# 3V3.net
KiCad netlist of a schematic drawn in Altium Designer
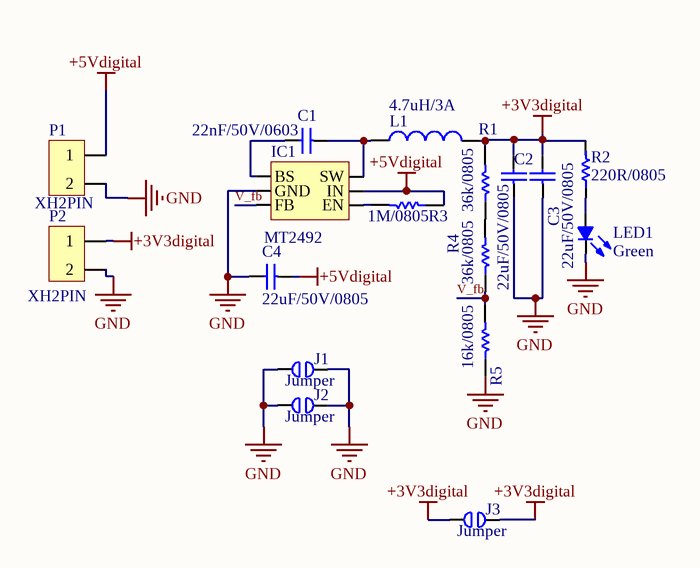
[diagram p0: 3V3.SchDoc]

(export (version "E")
  (design (tool "Eeschema 10.0.6"))
  (components
    (comp (ref "C1")
      (value "22nF/50V/0603")
      (footprint "cap 0603")
      (description "Capacitor")
      (libsource (lib "Schlib") (part "Capacitor"))
    )
    (comp (ref "C2")
      (value "22uF/50V/0805")
      (footprint "CAP 0805")
      (description "Capacitor")
      (libsource (lib "Schlib") (part "Capacitor"))
    )
    (comp (ref "C3")
      (value "22uF/50V/0805")
      (footprint "CAP 0805")
      (description "Capacitor")
      (libsource (lib "Schlib") (part "Capacitor"))
    )
    (comp (ref "C4")
      (value "22uF/50V/0805")
      (footprint "CAP 0805")
      (description "Capacitor")
      (libsource (lib "Schlib") (part "Capacitor"))
    )
    (comp (ref "IC1") (value "MT2492") (footprint "SOT23-6") (libsource (lib "Schlib") (part "ME3116AM6G")))
    (comp (ref "J1") (value "Jumper") (footprint "JUMPER 11MM") (libsource (lib "Schlib") (part "Jumper")))
    (comp (ref "J2") (value "Jumper") (footprint "JUMPER 11MM") (libsource (lib "Schlib") (part "Jumper")))
    (comp (ref "J3") (value "Jumper") (footprint "JUMPER 11MM") (libsource (lib "Schlib") (part "Jumper")))
    (comp (ref "L1")
      (value "4.7uH/3A")
      (footprint "5030")
      (description "Inductor")
      (libsource (lib "PFC NCP1653A 1KW") (part "Inductor"))
    )
    (comp (ref "LED1")
      (value "LED 3mm/Green")
      (footprint "LED 3mm")
      (description "Typical LED")
      (fields (field (name "COLOR") "Green"))
      (libsource (lib "TL494 12V-20A-KARA") (part "LED"))
    )
    (comp (ref "P1")
      (value "XH2PIN")
      (footprint "pin-header 2*1")
      (description "RELAY")
      (fields (field (name "PUBLISHER") "Altium Limited"))
      (libsource (lib "Schlib") (part "Header 2H"))
    )
    (comp (ref "P2")
      (value "XH2PIN")
      (footprint "pin-header 2*1")
      (description "RELAY")
      (fields (field (name "PUBLISHER") "Altium Limited"))
      (libsource (lib "Schlib") (part "Header 2H"))
    )
    (comp (ref "R1")
      (value "36k/0805")
      (footprint "Resistor 0603")
      (description "Resistor")
      (fields (field (name "PUBLISHER") "Altium Limited"))
      (libsource (lib "Miscellaneous Devices") (part "Res1"))
    )
    (comp (ref "R2") (value "220R/0805") (footprint "RES 0805") (libsource (lib "Schlib") (part "Res")))
    (comp (ref "R3")
      (value "1M/0805")
      (footprint "RES 0805")
      (description "Resistor")
      (fields (field (name "PUBLISHER") "Altium Limited"))
      (libsource (lib "Miscellaneous Devices") (part "Res1"))
    )
    (comp (ref "R4")
      (value "36k/0805")
      (footprint "Resistor 0603")
      (description "Resistor")
      (fields (field (name "PUBLISHER") "Altium Limited"))
      (libsource (lib "Miscellaneous Devices") (part "Res1"))
    )
    (comp (ref "R5")
      (value "16k/0805")
      (footprint "Resistor 0603")
      (description "Resistor")
      (fields (field (name "PUBLISHER") "Altium Limited"))
      (libsource (lib "Miscellaneous Devices") (part "Res1"))
    )
  )
  (nets
    (net (code "1") (name "+3V3digital") (class "Default")
      (node (ref "C2") (pin "1") (pinfunction "+_1") (pintype "passive"))
      (node (ref "C3") (pin "1") (pinfunction "+_1") (pintype "passive"))
      (node (ref "J3") (pin "1") (pinfunction "1_1") (pintype "passive"))
      (node (ref "J3") (pin "2") (pinfunction "2_2") (pintype "passive"))
      (node (ref "L1") (pin "2") (pinfunction "2_2") (pintype "passive"))
      (node (ref "P2") (pin "1") (pinfunction "1_1") (pintype "passive"))
      (node (ref "R1") (pin "2") (pinfunction "2_2") (pintype "passive"))
      (node (ref "R2") (pin "2") (pinfunction "2_2") (pintype "passive"))
    )
    (net (code "2") (name "+5Vdigital") (class "Default")
      (node (ref "C4") (pin "2") (pinfunction "-_2") (pintype "passive"))
      (node (ref "IC1") (pin "5") (pinfunction "IN_5") (pintype "passive"))
      (node (ref "P1") (pin "1") (pinfunction "1_1") (pintype "passive"))
      (node (ref "R3") (pin "1") (pinfunction "1_1") (pintype "passive"))
    )
    (net (code "3") (name "/V_fb") (class "Default")
      (node (ref "IC1") (pin "3") (pinfunction "FB_3") (pintype "passive"))
      (node (ref "R4") (pin "1") (pinfunction "1_1") (pintype "passive"))
      (node (ref "R5") (pin "2") (pinfunction "2_2") (pintype "passive"))
    )
    (net (code "4") (name "GND") (class "Default")
      (node (ref "C2") (pin "2") (pinfunction "-_2") (pintype "passive"))
      (node (ref "C3") (pin "2") (pinfunction "-_2") (pintype "passive"))
      (node (ref "C4") (pin "1") (pinfunction "+_1") (pintype "passive"))
      (node (ref "IC1") (pin "2") (pinfunction "GND_2") (pintype "passive"))
      (node (ref "J1") (pin "1") (pinfunction "1_1") (pintype "passive"))
      (node (ref "J1") (pin "2") (pinfunction "2_2") (pintype "passive"))
      (node (ref "J2") (pin "1") (pinfunction "1_1") (pintype "passive"))
      (node (ref "J2") (pin "2") (pinfunction "2_2") (pintype "passive"))
      (node (ref "LED1") (pin "2") (pinfunction "K_2") (pintype "passive"))
      (node (ref "P1") (pin "2") (pinfunction "2_2") (pintype "passive"))
      (node (ref "P2") (pin "2") (pinfunction "2_2") (pintype "passive"))
      (node (ref "R5") (pin "1") (pinfunction "1_1") (pintype "passive"))
    )
    (net (code "5") (name "Net-(C1-+)") (class "Default")
      (node (ref "C1") (pin "1") (pinfunction "+_1") (pintype "passive"))
      (node (ref "IC1") (pin "1") (pinfunction "BS_1") (pintype "passive"))
    )
    (net (code "6") (name "Net-(C1--)") (class "Default")
      (node (ref "C1") (pin "2") (pinfunction "-_2") (pintype "passive"))
      (node (ref "IC1") (pin "6") (pinfunction "SW_6") (pintype "passive"))
      (node (ref "L1") (pin "1") (pinfunction "1_1") (pintype "passive"))
    )
    (net (code "7") (name "Net-(IC1-EN)") (class "Default")
      (node (ref "IC1") (pin "4") (pinfunction "EN_4") (pintype "passive"))
      (node (ref "R3") (pin "2") (pinfunction "2_2") (pintype "passive"))
    )
    (net (code "8") (name "Net-(LED1-A)") (class "Default")
      (node (ref "LED1") (pin "1") (pinfunction "A_1") (pintype "passive"))
      (node (ref "R2") (pin "1") (pinfunction "1_1") (pintype "passive"))
    )
    (net (code "9") (name "Net-(R1-Pad1)") (class "Default")
      (node (ref "R1") (pin "1") (pinfunction "1_1") (pintype "passive"))
      (node (ref "R4") (pin "2") (pinfunction "2_2") (pintype "passive"))
    )
  )
)
